# Button.net
KiCad netlist of a schematic drawn in Altium Designer
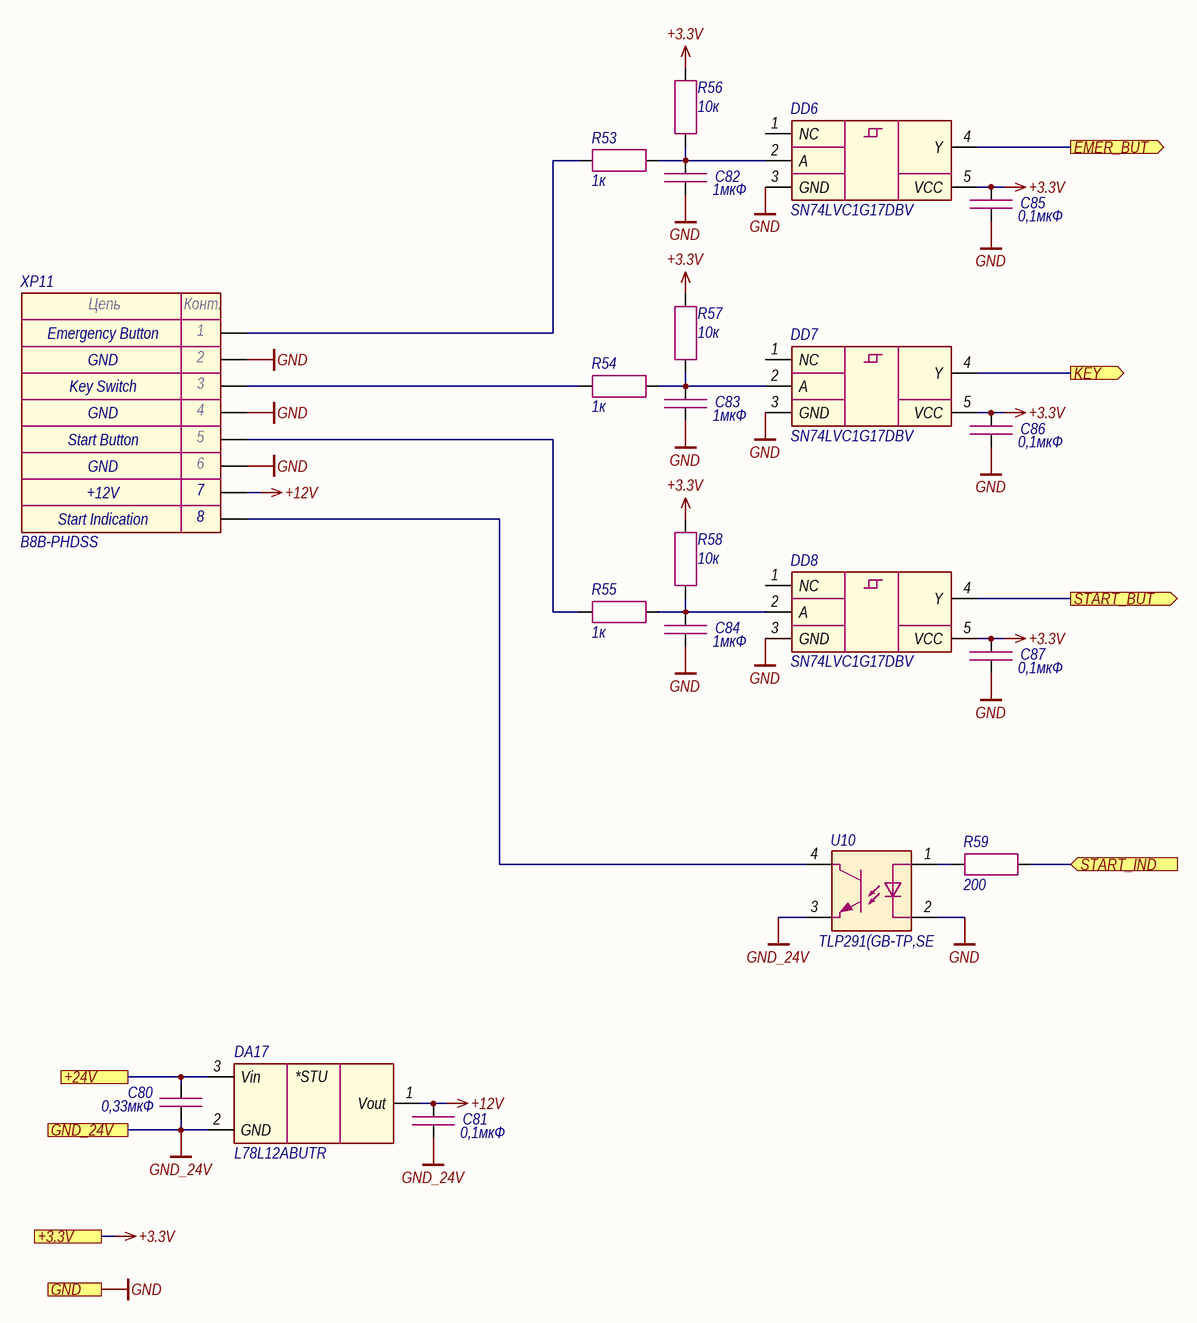
[diagram p0: Button.SchDoc]

(export (version "E")
  (design (tool "Eeschema 10.0.6"))
  (components
    (comp (ref "C80")
      (value "0,33мкФ")
      (footprint "Pcb_library:CAP_0805")
      (fields (field (name "MANUFACTURER") "Murata"))
      (libsource (lib "Schem_library") (part "Capacitor"))
    )
    (comp (ref "C81")
      (value "0,1мкФ")
      (footprint "Pcb_library:CAP_0603")
      (fields (field (name "MANUFACTURER") "Murata"))
      (libsource (lib "Schem_library") (part "Capacitor"))
    )
    (comp (ref "C82")
      (value "1мкФ")
      (footprint "Pcb_library:CAP_0603")
      (fields (field (name "MANUFACTURER") "Murata"))
      (libsource (lib "Schem_library") (part "Capacitor"))
    )
    (comp (ref "C83")
      (value "1мкФ")
      (footprint "Pcb_library:CAP_0603")
      (fields (field (name "MANUFACTURER") "Murata"))
      (libsource (lib "Schem_library") (part "Capacitor"))
    )
    (comp (ref "C84")
      (value "1мкФ")
      (footprint "Pcb_library:CAP_0603")
      (fields (field (name "MANUFACTURER") "Murata"))
      (libsource (lib "Schem_library") (part "Capacitor"))
    )
    (comp (ref "C85")
      (value "0,1мкФ")
      (footprint "Pcb_library:CAP_0603")
      (fields (field (name "MANUFACTURER") "Murata"))
      (libsource (lib "Schem_library") (part "Capacitor"))
    )
    (comp (ref "C86")
      (value "0,1мкФ")
      (footprint "Pcb_library:CAP_0603")
      (fields (field (name "MANUFACTURER") "Murata"))
      (libsource (lib "Schem_library") (part "Capacitor"))
    )
    (comp (ref "C87")
      (value "0,1мкФ")
      (footprint "Pcb_library:CAP_0603")
      (fields (field (name "MANUFACTURER") "Murata"))
      (libsource (lib "Schem_library") (part "Capacitor"))
    )
    (comp (ref "DA17")
      (value "L78L12ABUTR")
      (footprint "Pcb_library:SOT-89")
      (fields (field (name "MANUFACTURER") "STMicroelectronics"))
      (libsource (lib "Schem_library") (part "LD2981ABU50TR"))
    )
    (comp (ref "DD6")
      (value "SN74LVC1G17DBV")
      (footprint "Pcb_library:SOT-23-5")
      (fields (field (name "MANUFACTURER") "Texas Instruments"))
      (libsource (lib "Schem_library") (part "SN74LVC1G17"))
    )
    (comp (ref "DD7")
      (value "SN74LVC1G17DBV")
      (footprint "Pcb_library:SOT-23-5")
      (fields (field (name "MANUFACTURER") "Texas Instruments"))
      (libsource (lib "Schem_library") (part "SN74LVC1G17"))
    )
    (comp (ref "DD8")
      (value "SN74LVC1G17DBV")
      (footprint "Pcb_library:SOT-23-5")
      (fields (field (name "MANUFACTURER") "Texas Instruments"))
      (libsource (lib "Schem_library") (part "SN74LVC1G17"))
    )
    (comp (ref "R53")
      (value "1к")
      (footprint "Pcb_library:RES_0603")
      (fields (field (name "MANUFACTURER") "Yageo"))
      (libsource (lib "Schem_library") (part "Resistor"))
    )
    (comp (ref "R54")
      (value "1к")
      (footprint "Pcb_library:RES_0603")
      (fields (field (name "MANUFACTURER") "Yageo"))
      (libsource (lib "Schem_library") (part "Resistor"))
    )
    (comp (ref "R55")
      (value "1к")
      (footprint "Pcb_library:RES_0603")
      (fields (field (name "MANUFACTURER") "Yageo"))
      (libsource (lib "Schem_library") (part "Resistor"))
    )
    (comp (ref "R56")
      (value "10к")
      (footprint "Pcb_library:RES_0603")
      (fields (field (name "MANUFACTURER") "Yageo"))
      (libsource (lib "Schem_library") (part "Resistor"))
    )
    (comp (ref "R57")
      (value "10к")
      (footprint "Pcb_library:RES_0603")
      (fields (field (name "MANUFACTURER") "Yageo"))
      (libsource (lib "Schem_library") (part "Resistor"))
    )
    (comp (ref "R58")
      (value "10к")
      (footprint "Pcb_library:RES_0603")
      (fields (field (name "MANUFACTURER") "Yageo"))
      (libsource (lib "Schem_library") (part "Resistor"))
    )
    (comp (ref "R59")
      (value "200")
      (footprint "Pcb_library:RES_0603")
      (fields (field (name "MANUFACTURER") "Yageo"))
      (libsource (lib "Schem_library") (part "Resistor"))
    )
    (comp (ref "U10")
      (value "TLP291(GB-TP,SE")
      (footprint "Pcb_library:11-3C1")
      (fields (field (name "MANUFACTURER") "Toshiba"))
      (libsource (lib "Schem_library") (part "TLP291"))
    )
    (comp (ref "XP11")
      (value "B8B-PHDSS")
      (footprint "Pcb_library:B8B-PHDSS")
      (fields (field (name "MANUFACTURER") "JST"))
      (libsource (lib "Schem_library") (part "Connector-8"))
    )
  )
  (nets
    (net (code "1") (name "+3.3V") (class "Default")
      (node (ref "C85") (pin "1") (pinfunction "1_1") (pintype "passive"))
      (node (ref "C86") (pin "1") (pinfunction "1_1") (pintype "passive"))
      (node (ref "C87") (pin "1") (pinfunction "1_1") (pintype "passive"))
      (node (ref "DD6") (pin "5") (pinfunction "VCC_5") (pintype "passive"))
      (node (ref "DD7") (pin "5") (pinfunction "VCC_5") (pintype "passive"))
      (node (ref "DD8") (pin "5") (pinfunction "VCC_5") (pintype "passive"))
      (node (ref "R56") (pin "2") (pinfunction "2_2") (pintype "passive"))
      (node (ref "R57") (pin "2") (pinfunction "2_2") (pintype "passive"))
      (node (ref "R58") (pin "2") (pinfunction "2_2") (pintype "passive"))
    )
    (net (code "2") (name "+12V") (class "Default")
      (node (ref "C81") (pin "1") (pinfunction "1_1") (pintype "passive"))
      (node (ref "DA17") (pin "1") (pinfunction "Vout_1") (pintype "passive"))
      (node (ref "XP11") (pin "7") (pintype "passive"))
    )
    (net (code "3") (name "/+24V") (class "Default")
      (node (ref "C80") (pin "2") (pinfunction "2_2") (pintype "passive"))
      (node (ref "DA17") (pin "3") (pinfunction "Vin_3") (pintype "passive"))
    )
    (net (code "4") (name "/EMER_BUT") (class "Default")
      (node (ref "DD6") (pin "4") (pinfunction "Y_4") (pintype "passive"))
    )
    (net (code "5") (name "/KEY") (class "Default")
      (node (ref "DD7") (pin "4") (pinfunction "Y_4") (pintype "passive"))
    )
    (net (code "6") (name "/START_BUT") (class "Default")
      (node (ref "DD8") (pin "4") (pinfunction "Y_4") (pintype "passive"))
    )
    (net (code "7") (name "/START_IND") (class "Default")
      (node (ref "R59") (pin "2") (pinfunction "2_2") (pintype "passive"))
    )
    (net (code "8") (name "GND") (class "Default")
      (node (ref "C82") (pin "2") (pinfunction "2_2") (pintype "passive"))
      (node (ref "C83") (pin "2") (pinfunction "2_2") (pintype "passive"))
      (node (ref "C84") (pin "2") (pinfunction "2_2") (pintype "passive"))
      (node (ref "C85") (pin "2") (pinfunction "2_2") (pintype "passive"))
      (node (ref "C86") (pin "2") (pinfunction "2_2") (pintype "passive"))
      (node (ref "C87") (pin "2") (pinfunction "2_2") (pintype "passive"))
      (node (ref "DD6") (pin "3") (pinfunction "GND_3") (pintype "passive"))
      (node (ref "DD7") (pin "3") (pinfunction "GND_3") (pintype "passive"))
      (node (ref "DD8") (pin "3") (pinfunction "GND_3") (pintype "passive"))
      (node (ref "U10") (pin "2") (pintype "passive"))
      (node (ref "XP11") (pin "2") (pintype "passive"))
      (node (ref "XP11") (pin "4") (pintype "passive"))
      (node (ref "XP11") (pin "6") (pintype "passive"))
    )
    (net (code "9") (name "GND_24V") (class "Default")
      (node (ref "C80") (pin "1") (pinfunction "1_1") (pintype "passive"))
      (node (ref "C81") (pin "2") (pinfunction "2_2") (pintype "passive"))
      (node (ref "DA17") (pin "2") (pinfunction "GND_2") (pintype "passive"))
      (node (ref "U10") (pin "3") (pintype "passive"))
    )
    (net (code "10") (name "Net-(DD6-A)") (class "Default")
      (node (ref "C82") (pin "1") (pinfunction "1_1") (pintype "passive"))
      (node (ref "DD6") (pin "2") (pinfunction "A_2") (pintype "passive"))
      (node (ref "R53") (pin "2") (pinfunction "2_2") (pintype "passive"))
      (node (ref "R56") (pin "1") (pinfunction "1_1") (pintype "passive"))
    )
    (net (code "11") (name "Net-(DD7-A)") (class "Default")
      (node (ref "C83") (pin "1") (pinfunction "1_1") (pintype "passive"))
      (node (ref "DD7") (pin "2") (pinfunction "A_2") (pintype "passive"))
      (node (ref "R54") (pin "2") (pinfunction "2_2") (pintype "passive"))
      (node (ref "R57") (pin "1") (pinfunction "1_1") (pintype "passive"))
    )
    (net (code "12") (name "Net-(DD8-A)") (class "Default")
      (node (ref "C84") (pin "1") (pinfunction "1_1") (pintype "passive"))
      (node (ref "DD8") (pin "2") (pinfunction "A_2") (pintype "passive"))
      (node (ref "R55") (pin "2") (pinfunction "2_2") (pintype "passive"))
      (node (ref "R58") (pin "1") (pinfunction "1_1") (pintype "passive"))
    )
    (net (code "13") (name "Net-(R53-Pad1)") (class "Default")
      (node (ref "R53") (pin "1") (pinfunction "1_1") (pintype "passive"))
      (node (ref "XP11") (pin "1") (pintype "passive"))
    )
    (net (code "14") (name "Net-(R54-Pad1)") (class "Default")
      (node (ref "R54") (pin "1") (pinfunction "1_1") (pintype "passive"))
      (node (ref "XP11") (pin "3") (pintype "passive"))
    )
    (net (code "15") (name "Net-(R55-Pad1)") (class "Default")
      (node (ref "R55") (pin "1") (pinfunction "1_1") (pintype "passive"))
      (node (ref "XP11") (pin "5") (pintype "passive"))
    )
    (net (code "16") (name "Net-(R59-Pad1)") (class "Default")
      (node (ref "R59") (pin "1") (pinfunction "1_1") (pintype "passive"))
      (node (ref "U10") (pin "1") (pintype "passive"))
    )
    (net (code "17") (name "Net-(U10-Pad4)") (class "Default")
      (node (ref "U10") (pin "4") (pintype "passive"))
      (node (ref "XP11") (pin "8") (pintype "passive"))
    )
    (net (code "18") (name "unconnected-(DD6-NC-Pad1)") (class "Default")
      (node (ref "DD6") (pin "1") (pinfunction "NC_1") (pintype "passive"))
    )
    (net (code "19") (name "unconnected-(DD7-NC-Pad1)") (class "Default")
      (node (ref "DD7") (pin "1") (pinfunction "NC_1") (pintype "passive"))
    )
    (net (code "20") (name "unconnected-(DD8-NC-Pad1)") (class "Default")
      (node (ref "DD8") (pin "1") (pinfunction "NC_1") (pintype "passive"))
    )
  )
)
